# FLASH_M25PX0_SPI_8Mbit.net
KiCad netlist of a schematic drawn in Altium Designer
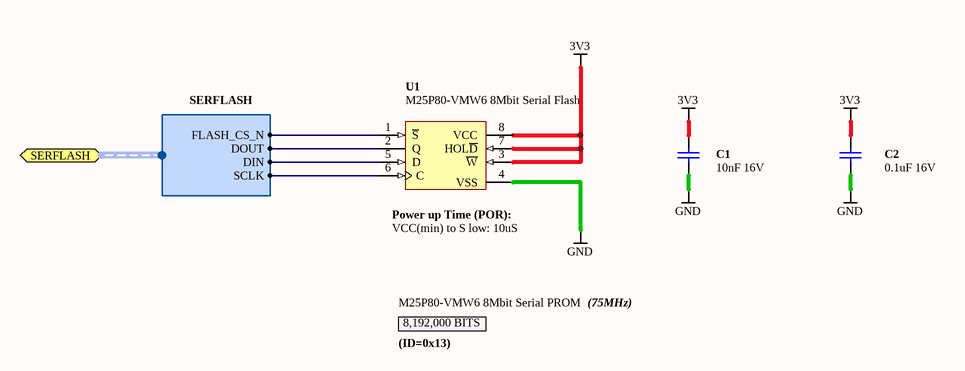
[diagram p0: FLASH_M25PX0_SPI_8Mbit.SchDoc]

(export (version "E")
  (design (tool "Eeschema 10.0.6"))
  (components
    (comp (ref "C1")
      (value "10nF 16V")
      (footprint "CAPC1005-STAR")
      (description "Capacitor, Ceramic, 10nF 10% 16V 0402 (1005) X7R")
      (fields (field (name "TOLERANCE") "10 %"))
      (libsource (lib "altium-import") (part "root_0_CAP-NP_"))
    )
    (comp (ref "C2")
      (value "0.1uF 16V")
      (footprint "CAPC1005-STAR")
      (description "Capacitor, Ceramic, 0.1uF 10% 16V 0402 (1005) X7R")
      (fields (field (name "TOLERANCE") "10 %"))
      (libsource (lib "altium-import") (part "root_2_CAP-NP_"))
    )
    (comp (ref "U1")
      (value "M25P80-VMW6 8Mbit Serial Flash")
      (footprint "SOIC8-200-BODY")
      (libsource (lib "altium-import") (part "root_0_M25P80_"))
    )
  )
  (nets
    (net (code "2") (name "/DIN") (class "Default")
      (node (ref "U1") (pin "5") (pinfunction "D_5") (pintype "input"))
    )
    (net (code "3") (name "/DOUT") (class "Default")
      (node (ref "U1") (pin "2") (pinfunction "Q_2") (pintype "tri_state"))
    )
    (net (code "4") (name "/FLASH_CS_N") (class "Default")
      (node (ref "U1") (pin "1") (pinfunction "~{S}_1") (pintype "input"))
    )
    (net (code "5") (name "/SCLK") (class "Default")
      (node (ref "U1") (pin "6") (pinfunction "C_6") (pintype "input"))
    )
    (net (code "7") (name "3V3") (class "Default")
      (node (ref "C1") (pin "1") (pinfunction "1_1") (pintype "passive"))
      (node (ref "C2") (pin "2") (pinfunction "2_2") (pintype "passive"))
      (node (ref "U1") (pin "3") (pinfunction "~{W}_3") (pintype "input"))
      (node (ref "U1") (pin "7") (pinfunction "HOL~{D}_7") (pintype "input"))
      (node (ref "U1") (pin "8") (pinfunction "VCC_8") (pintype "power_in"))
    )
    (net (code "8") (name "GND") (class "Default")
      (node (ref "C1") (pin "2") (pinfunction "2_2") (pintype "passive"))
      (node (ref "C2") (pin "1") (pinfunction "1_1") (pintype "passive"))
      (node (ref "U1") (pin "4") (pinfunction "VSS_4") (pintype "power_in"))
    )
  )
)
